# Zasil.net
KiCad netlist of a schematic drawn in Altium Designer
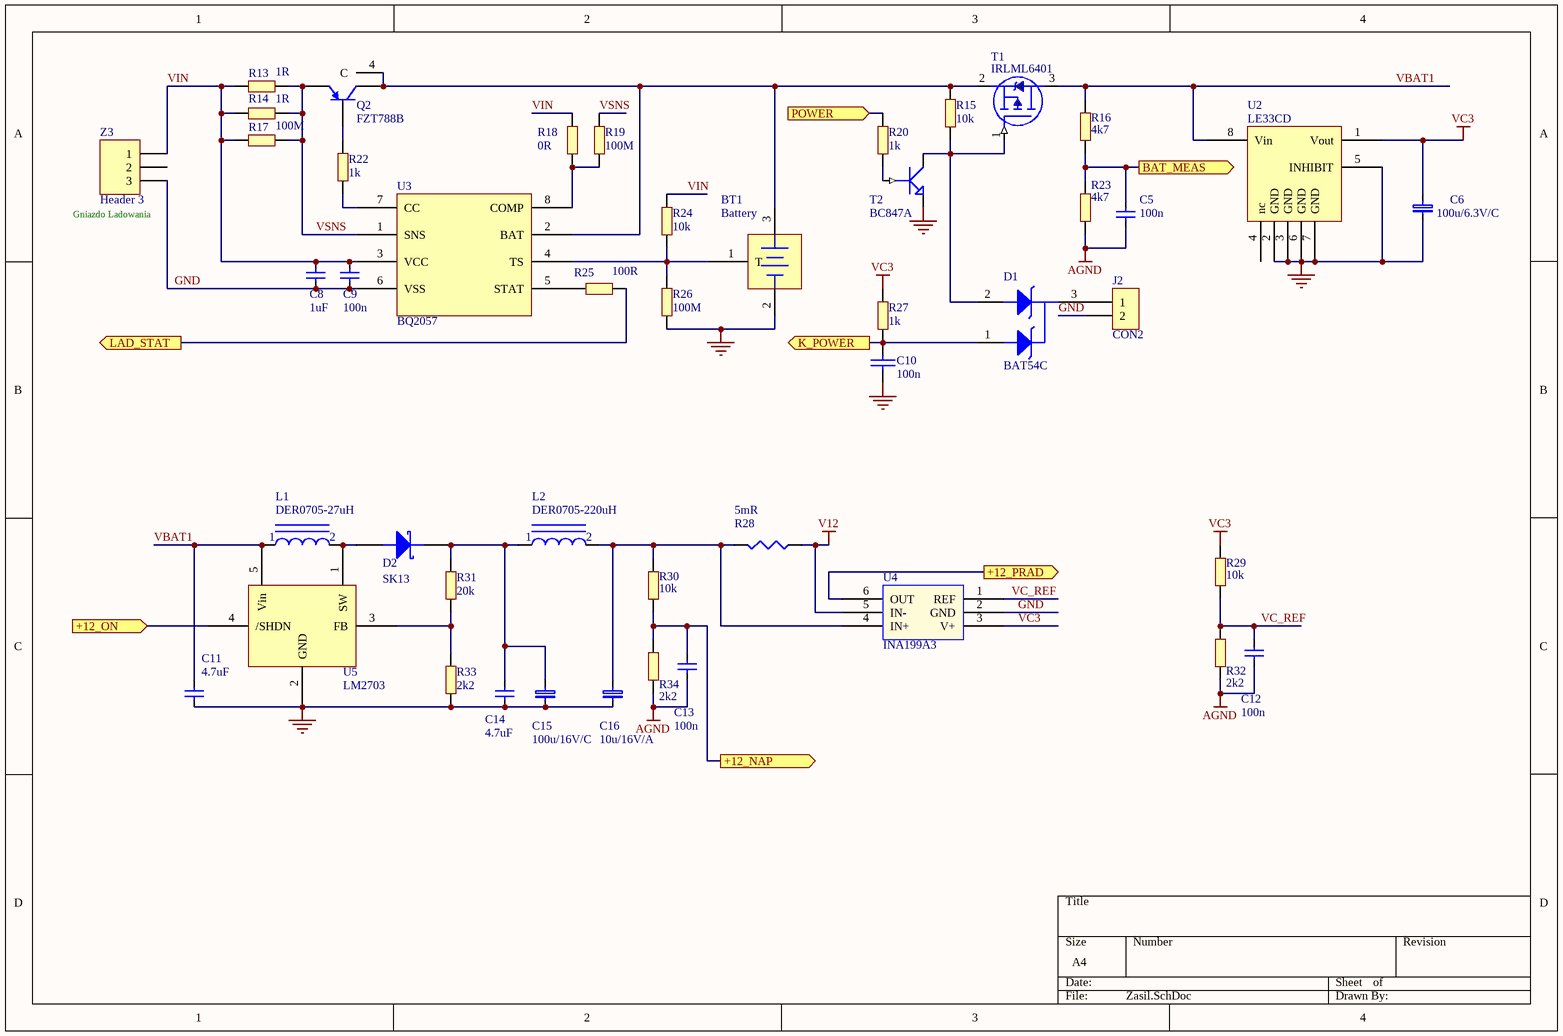
[diagram p0: Zasil.SchDoc]

(export (version "E")
  (design (tool "Eeschema 10.0.6"))
  (components
    (comp (ref "BT1")
      (value "Battery")
      (footprint "BAT4")
      (description "Multicell Battery")
      (fields (field (name "PUBLISHER") "*"))
      (libsource (lib "*") (part "BAT_TEL"))
    )
    (comp (ref "C5") (value "100n") (footprint "0603C") (libsource (lib "*") (part "CAP")))
    (comp (ref "C6")
      (value "100u/6.3V/C")
      (footprint "CAP_C")
      (description "KONDENSATOR ELEKTROLITYCZNY TANTALOWY SMD")
      (libsource (lib "*") (part "CAP_TANTAL_SMD"))
    )
    (comp (ref "C8") (value "1uF") (footprint "0603C") (libsource (lib "*") (part "CAP")))
    (comp (ref "C9") (value "100n") (footprint "0603C") (libsource (lib "*") (part "CAP")))
    (comp (ref "C10")
      (value "100n")
      (footprint "0603C")
      (description "Capacitor")
      (libsource (lib "") (part "CAP_1"))
    )
    (comp (ref "C11") (value "4.7uF") (footprint "1206") (libsource (lib "*") (part "CAP")))
    (comp (ref "C12") (value "100n") (footprint "0603C") (libsource (lib "*") (part "CAP")))
    (comp (ref "C13") (value "100n") (footprint "0603C") (libsource (lib "*") (part "CAP")))
    (comp (ref "C14") (value "4.7uF") (footprint "1206") (libsource (lib "*") (part "CAP")))
    (comp (ref "C15")
      (value "100u/16V/C")
      (footprint "CAP_C")
      (description "KONDENSATOR ELEKTROLITYCZNY TANTALOWY SMD")
      (libsource (lib "*") (part "CAP_TANTAL_SMD"))
    )
    (comp (ref "C16")
      (value "10u/16V/A")
      (footprint "CAP_A")
      (description "KONDENSATOR ELEKTROLITYCZNY TANTALOWY SMD")
      (libsource (lib "*") (part "CAP_TANTAL_SMD"))
    )
    (comp (ref "D1") (value "BAT54C") (footprint "SOT23") (libsource (lib "*") (part "BAT54C")))
    (comp (ref "D2")
      (value "SK13")
      (footprint "RD5")
      (description "Schottky Diode")
      (libsource (lib "*") (part "DIODE SCHOTTKY"))
    )
    (comp (ref "J2")
      (value "CON2")
      (footprint "SIP2")
      (description "Connector")
      (libsource (lib "*") (part "CON2"))
    )
    (comp (ref "L1") (value "DER0705-27uH") (footprint "DER0705") (libsource (lib "*") (part "CEWKA_1")))
    (comp (ref "L2") (value "DER0705-220uH") (footprint "DER0705") (libsource (lib "*") (part "CEWKA_1")))
    (comp (ref "Q2")
      (value "FZT788B")
      (footprint "MP04A_N1")
      (fields (field (name "PUBLISHER") "Altium Limited"))
      (libsource (lib "*") (part "PNP"))
    )
    (comp (ref "R13") (value "1R") (footprint "0805R") (libsource (lib "*") (part "RES3")))
    (comp (ref "R14") (value "1R") (footprint "0805R") (libsource (lib "*") (part "RES3")))
    (comp (ref "R15") (value "10k") (footprint "0603R") (libsource (lib "") (part "RES3_2")))
    (comp (ref "R16") (value "4k7") (footprint "0603R") (libsource (lib "") (part "RES3_2")))
    (comp (ref "R17") (value "100M") (footprint "0805R") (libsource (lib "*") (part "RES3")))
    (comp (ref "R18") (value "0R") (footprint "0603R") (libsource (lib "") (part "RES3_1")))
    (comp (ref "R19") (value "100M") (footprint "0603R") (libsource (lib "") (part "RES3_1")))
    (comp (ref "R20") (value "1k") (footprint "0603R") (libsource (lib "") (part "RES3_2")))
    (comp (ref "R22") (value "1k") (footprint "0603R") (libsource (lib "") (part "RES3_1")))
    (comp (ref "R23") (value "4k7") (footprint "0603R") (libsource (lib "") (part "RES3_2")))
    (comp (ref "R24") (value "10k") (footprint "0603R") (libsource (lib "") (part "RES3_1")))
    (comp (ref "R25") (value "100R") (footprint "0603R") (libsource (lib "*") (part "RES3")))
    (comp (ref "R26") (value "100M") (footprint "0603R") (libsource (lib "") (part "RES3_1")))
    (comp (ref "R27") (value "1k") (footprint "0603R") (libsource (lib "") (part "RES3_2")))
    (comp (ref "R28") (value "5mR") (footprint "1206R") (libsource (lib "*") (part "RES1")))
    (comp (ref "R29") (value "10k") (footprint "0603R") (libsource (lib "") (part "RES3_2")))
    (comp (ref "R30") (value "10k") (footprint "0603R") (libsource (lib "") (part "RES3_2")))
    (comp (ref "R31") (value "20k") (footprint "0603R") (libsource (lib "") (part "RES3_1")))
    (comp (ref "R32") (value "2k2") (footprint "0603R") (libsource (lib "") (part "RES3_2")))
    (comp (ref "R33") (value "2k2") (footprint "0603R") (libsource (lib "") (part "RES3_1")))
    (comp (ref "R34") (value "2k2") (footprint "0603R") (libsource (lib "") (part "RES3_2")))
    (comp (ref "T1")
      (value "IRLML6401")
      (footprint "SOT23")
      (description "Low Charge N-Channel MOSFET")
      (libsource (lib "*") (part "IRLML9303"))
    )
    (comp (ref "T2")
      (value "BC847A")
      (footprint "SOT23")
      (description "NPN Transistor")
      (libsource (lib "*") (part "BC847A"))
    )
    (comp (ref "U2") (value "LE33CD") (footprint "SO8") (libsource (lib "*") (part "LE33")))
    (comp (ref "U3") (value "BQ2057") (footprint "SO8") (libsource (lib "*") (part "BQ2057")))
    (comp (ref "U4") (value "INA199A3") (footprint "SC70-6") (libsource (lib "GkSchlib") (part "INA199")))
    (comp (ref "U5") (value "LM2703") (footprint "SOT23-5") (libsource (lib "*") (part "LM2703")))
    (comp (ref "Z3")
      (value "Header 3")
      (footprint "PIN3_2.5")
      (description "Header, 3-Pin")
      (fields (field (name "PUBLISHER") "Altium Limited"))
      (libsource (lib "*") (part "Header 3"))
    )
  )
  (nets
    (net (code "1") (name "/+12_NAP") (class "Default")
      (node (ref "C13") (pin "1") (pintype "passive"))
      (node (ref "R30") (pin "1") (pintype "passive"))
      (node (ref "R34") (pin "2") (pintype "passive"))
    )
    (net (code "2") (name "/+12_ON") (class "Default")
      (node (ref "U5") (pin "4") (pinfunction "/SHDN_4") (pintype "passive"))
    )
    (net (code "3") (name "/+12_PRAD") (class "Default")
      (node (ref "U4") (pin "6") (pinfunction "OUT_6") (pintype "passive"))
    )
    (net (code "4") (name "/BAT_MEAS") (class "Default")
      (node (ref "C5") (pin "1") (pintype "passive"))
      (node (ref "R16") (pin "1") (pintype "passive"))
      (node (ref "R23") (pin "2") (pintype "passive"))
    )
    (net (code "5") (name "/K_POWER") (class "Default")
      (node (ref "C10") (pin "1") (pinfunction "1_1") (pintype "passive"))
      (node (ref "D1") (pin "1") (pinfunction "A1_1") (pintype "passive"))
      (node (ref "R27") (pin "1") (pintype "passive"))
    )
    (net (code "6") (name "/LAD_STAT") (class "Default") (node (ref "R25") (pin "2") (pintype "passive")))
    (net (code "7") (name "/POWER") (class "Default") (node (ref "R20") (pin "2") (pintype "passive")))
    (net (code "8") (name "/VBAT1") (class "Default")
      (node (ref "C11") (pin "1") (pintype "passive"))
      (node (ref "L1") (pin "1") (pintype "passive"))
      (node (ref "R16") (pin "2") (pintype "passive"))
      (node (ref "T1") (pin "3") (pinfunction "DRAIN_3") (pintype "passive"))
      (node (ref "U2") (pin "8") (pinfunction "Vin_8") (pintype "passive"))
      (node (ref "U5") (pin "5") (pinfunction "Vin_5") (pintype "passive"))
    )
    (net (code "9") (name "/VC_REF") (class "Default")
      (node (ref "C12") (pin "1") (pintype "passive"))
      (node (ref "R29") (pin "1") (pintype "passive"))
      (node (ref "R32") (pin "2") (pintype "passive"))
      (node (ref "U4") (pin "1") (pinfunction "REF_1") (pintype "passive"))
    )
    (net (code "10") (name "/VIN") (class "Default")
      (node (ref "C8") (pin "1") (pintype "passive"))
      (node (ref "C9") (pin "1") (pintype "passive"))
      (node (ref "R13") (pin "1") (pintype "passive"))
      (node (ref "R14") (pin "1") (pintype "passive"))
      (node (ref "R17") (pin "1") (pintype "passive"))
      (node (ref "R18") (pin "1") (pintype "passive"))
      (node (ref "R24") (pin "1") (pintype "passive"))
      (node (ref "U3") (pin "3") (pinfunction "VCC_3") (pintype "passive"))
      (node (ref "Z3") (pin "1") (pinfunction "1_1") (pintype "passive"))
    )
    (net (code "11") (name "/VSNS") (class "Default")
      (node (ref "Q2") (pin "3") (pinfunction "E_3") (pintype "passive"))
      (node (ref "R13") (pin "2") (pintype "passive"))
      (node (ref "R14") (pin "2") (pintype "passive"))
      (node (ref "R17") (pin "2") (pintype "passive"))
      (node (ref "R19") (pin "1") (pintype "passive"))
      (node (ref "U3") (pin "1") (pinfunction "SNS_1") (pintype "passive"))
    )
    (net (code "12") (name "AGND") (class "Default")
      (node (ref "C12") (pin "2") (pintype "passive"))
      (node (ref "C13") (pin "2") (pintype "passive"))
      (node (ref "C5") (pin "2") (pintype "passive"))
      (node (ref "R23") (pin "1") (pintype "passive"))
      (node (ref "R32") (pin "1") (pintype "passive"))
      (node (ref "R34") (pin "1") (pintype "passive"))
    )
    (net (code "13") (name "GND") (class "Default")
      (node (ref "BT1") (pin "2") (pinfunction "-_2") (pintype "passive"))
      (node (ref "C10") (pin "2") (pinfunction "2_2") (pintype "passive"))
      (node (ref "C11") (pin "2") (pintype "passive"))
      (node (ref "C14") (pin "2") (pintype "passive"))
      (node (ref "C15") (pin "1") (pintype "passive"))
      (node (ref "C16") (pin "1") (pintype "passive"))
      (node (ref "C6") (pin "1") (pintype "passive"))
      (node (ref "C8") (pin "2") (pintype "passive"))
      (node (ref "C9") (pin "2") (pintype "passive"))
      (node (ref "J2") (pin "2") (pinfunction "2_2") (pintype "passive"))
      (node (ref "R26") (pin "2") (pintype "passive"))
      (node (ref "R33") (pin "2") (pintype "passive"))
      (node (ref "T2") (pin "2") (pinfunction "E_2") (pintype "passive"))
      (node (ref "U2") (pin "2") (pinfunction "GND_2") (pintype "passive"))
      (node (ref "U2") (pin "3") (pinfunction "GND_3") (pintype "passive"))
      (node (ref "U2") (pin "5") (pinfunction "INHIBIT_5") (pintype "passive"))
      (node (ref "U2") (pin "6") (pinfunction "GND_6") (pintype "passive"))
      (node (ref "U2") (pin "7") (pinfunction "GND_7") (pintype "passive"))
      (node (ref "U3") (pin "6") (pinfunction "VSS_6") (pintype "passive"))
      (node (ref "U4") (pin "2") (pinfunction "GND_2") (pintype "passive"))
      (node (ref "U5") (pin "2") (pinfunction "GND_2") (pintype "passive"))
      (node (ref "Z3") (pin "3") (pinfunction "3_3") (pintype "passive"))
    )
    (net (code "14") (name "Net-(BT1-+)") (class "Default")
      (node (ref "BT1") (pin "3") (pinfunction "+_3") (pintype "passive"))
      (node (ref "Q2") (pin "2") (pinfunction "C_2") (pintype "passive"))
      (node (ref "Q2") (pin "4") (pinfunction "C_4") (pintype "passive"))
      (node (ref "R15") (pin "2") (pintype "passive"))
      (node (ref "T1") (pin "2") (pinfunction "SOURCE_2") (pintype "passive"))
      (node (ref "U3") (pin "2") (pinfunction "BAT_2") (pintype "passive"))
    )
    (net (code "15") (name "Net-(BT1-T)") (class "Default")
      (node (ref "BT1") (pin "1") (pinfunction "T_1") (pintype "passive"))
      (node (ref "R24") (pin "2") (pintype "passive"))
      (node (ref "R26") (pin "1") (pintype "passive"))
      (node (ref "U3") (pin "4") (pinfunction "TS_4") (pintype "passive"))
    )
    (net (code "16") (name "Net-(C14-Pad1)") (class "Default")
      (node (ref "C14") (pin "1") (pintype "passive"))
      (node (ref "C15") (pin "2") (pintype "passive"))
      (node (ref "D2") (pin "K") (pinfunction "K_K") (pintype "passive"))
      (node (ref "L2") (pin "1") (pintype "passive"))
      (node (ref "R31") (pin "1") (pintype "passive"))
    )
    (net (code "17") (name "Net-(D1-A2)") (class "Default")
      (node (ref "D1") (pin "2") (pinfunction "A2_2") (pintype "passive"))
      (node (ref "R15") (pin "1") (pintype "passive"))
      (node (ref "T1") (pin "1") (pinfunction "GATE_1") (pintype "input"))
      (node (ref "T2") (pin "3") (pinfunction "C_3") (pintype "passive"))
    )
    (net (code "18") (name "Net-(D1-K)") (class "Default")
      (node (ref "D1") (pin "3") (pinfunction "K_3") (pintype "passive"))
      (node (ref "J2") (pin "1") (pinfunction "1_1") (pintype "passive"))
    )
    (net (code "19") (name "Net-(Q2-B)") (class "Default")
      (node (ref "Q2") (pin "1") (pinfunction "B_1") (pintype "passive"))
      (node (ref "R22") (pin "1") (pintype "passive"))
    )
    (net (code "20") (name "Net-(T2-B)") (class "Default")
      (node (ref "R20") (pin "1") (pintype "passive"))
      (node (ref "T2") (pin "1") (pinfunction "B_1") (pintype "input"))
    )
    (net (code "21") (name "Net-(U3-CC)") (class "Default")
      (node (ref "R22") (pin "2") (pintype "passive"))
      (node (ref "U3") (pin "7") (pinfunction "CC_7") (pintype "passive"))
    )
    (net (code "22") (name "Net-(U3-COMP)") (class "Default")
      (node (ref "R18") (pin "2") (pintype "passive"))
      (node (ref "R19") (pin "2") (pintype "passive"))
      (node (ref "U3") (pin "8") (pinfunction "COMP_8") (pintype "passive"))
    )
    (net (code "23") (name "Net-(U3-STAT)") (class "Default")
      (node (ref "R25") (pin "1") (pintype "passive"))
      (node (ref "U3") (pin "5") (pinfunction "STAT_5") (pintype "passive"))
    )
    (net (code "24") (name "Net-(U4-IN+)") (class "Default")
      (node (ref "C16") (pin "2") (pintype "passive"))
      (node (ref "L2") (pin "2") (pintype "passive"))
      (node (ref "R28") (pin "2") (pinfunction "2_2") (pintype "passive"))
      (node (ref "R30") (pin "2") (pintype "passive"))
      (node (ref "U4") (pin "4") (pinfunction "IN+_4") (pintype "passive"))
    )
    (net (code "25") (name "Net-(U5-FB)") (class "Default")
      (node (ref "R31") (pin "2") (pintype "passive"))
      (node (ref "R33") (pin "1") (pintype "passive"))
      (node (ref "U5") (pin "3") (pinfunction "FB_3") (pintype "passive"))
    )
    (net (code "26") (name "Net-(U5-SW)") (class "Default")
      (node (ref "D2") (pin "A") (pinfunction "A_A") (pintype "passive"))
      (node (ref "L1") (pin "2") (pintype "passive"))
      (node (ref "U5") (pin "1") (pinfunction "SW_1") (pintype "passive"))
    )
    (net (code "27") (name "V12") (class "Default")
      (node (ref "R28") (pin "1") (pinfunction "1_1") (pintype "passive"))
      (node (ref "U4") (pin "5") (pinfunction "IN-_5") (pintype "passive"))
    )
    (net (code "28") (name "VC3") (class "Default")
      (node (ref "C6") (pin "2") (pintype "passive"))
      (node (ref "R27") (pin "2") (pintype "passive"))
      (node (ref "R29") (pin "2") (pintype "passive"))
      (node (ref "U2") (pin "1") (pinfunction "Vout_1") (pintype "passive"))
      (node (ref "U4") (pin "3") (pinfunction "V+_3") (pintype "passive"))
    )
    (net (code "29") (name "unconnected-(U2-nc-Pad4)") (class "Default")
      (node (ref "U2") (pin "4") (pinfunction "nc_4") (pintype "passive"))
    )
    (net (code "30") (name "unconnected-(Z3-Pad2)") (class "Default")
      (node (ref "Z3") (pin "2") (pinfunction "2_2") (pintype "passive"))
    )
  )
)
